# SYZYGY_BOARD_CONN.net
KiCad netlist of a schematic drawn in Altium Designer
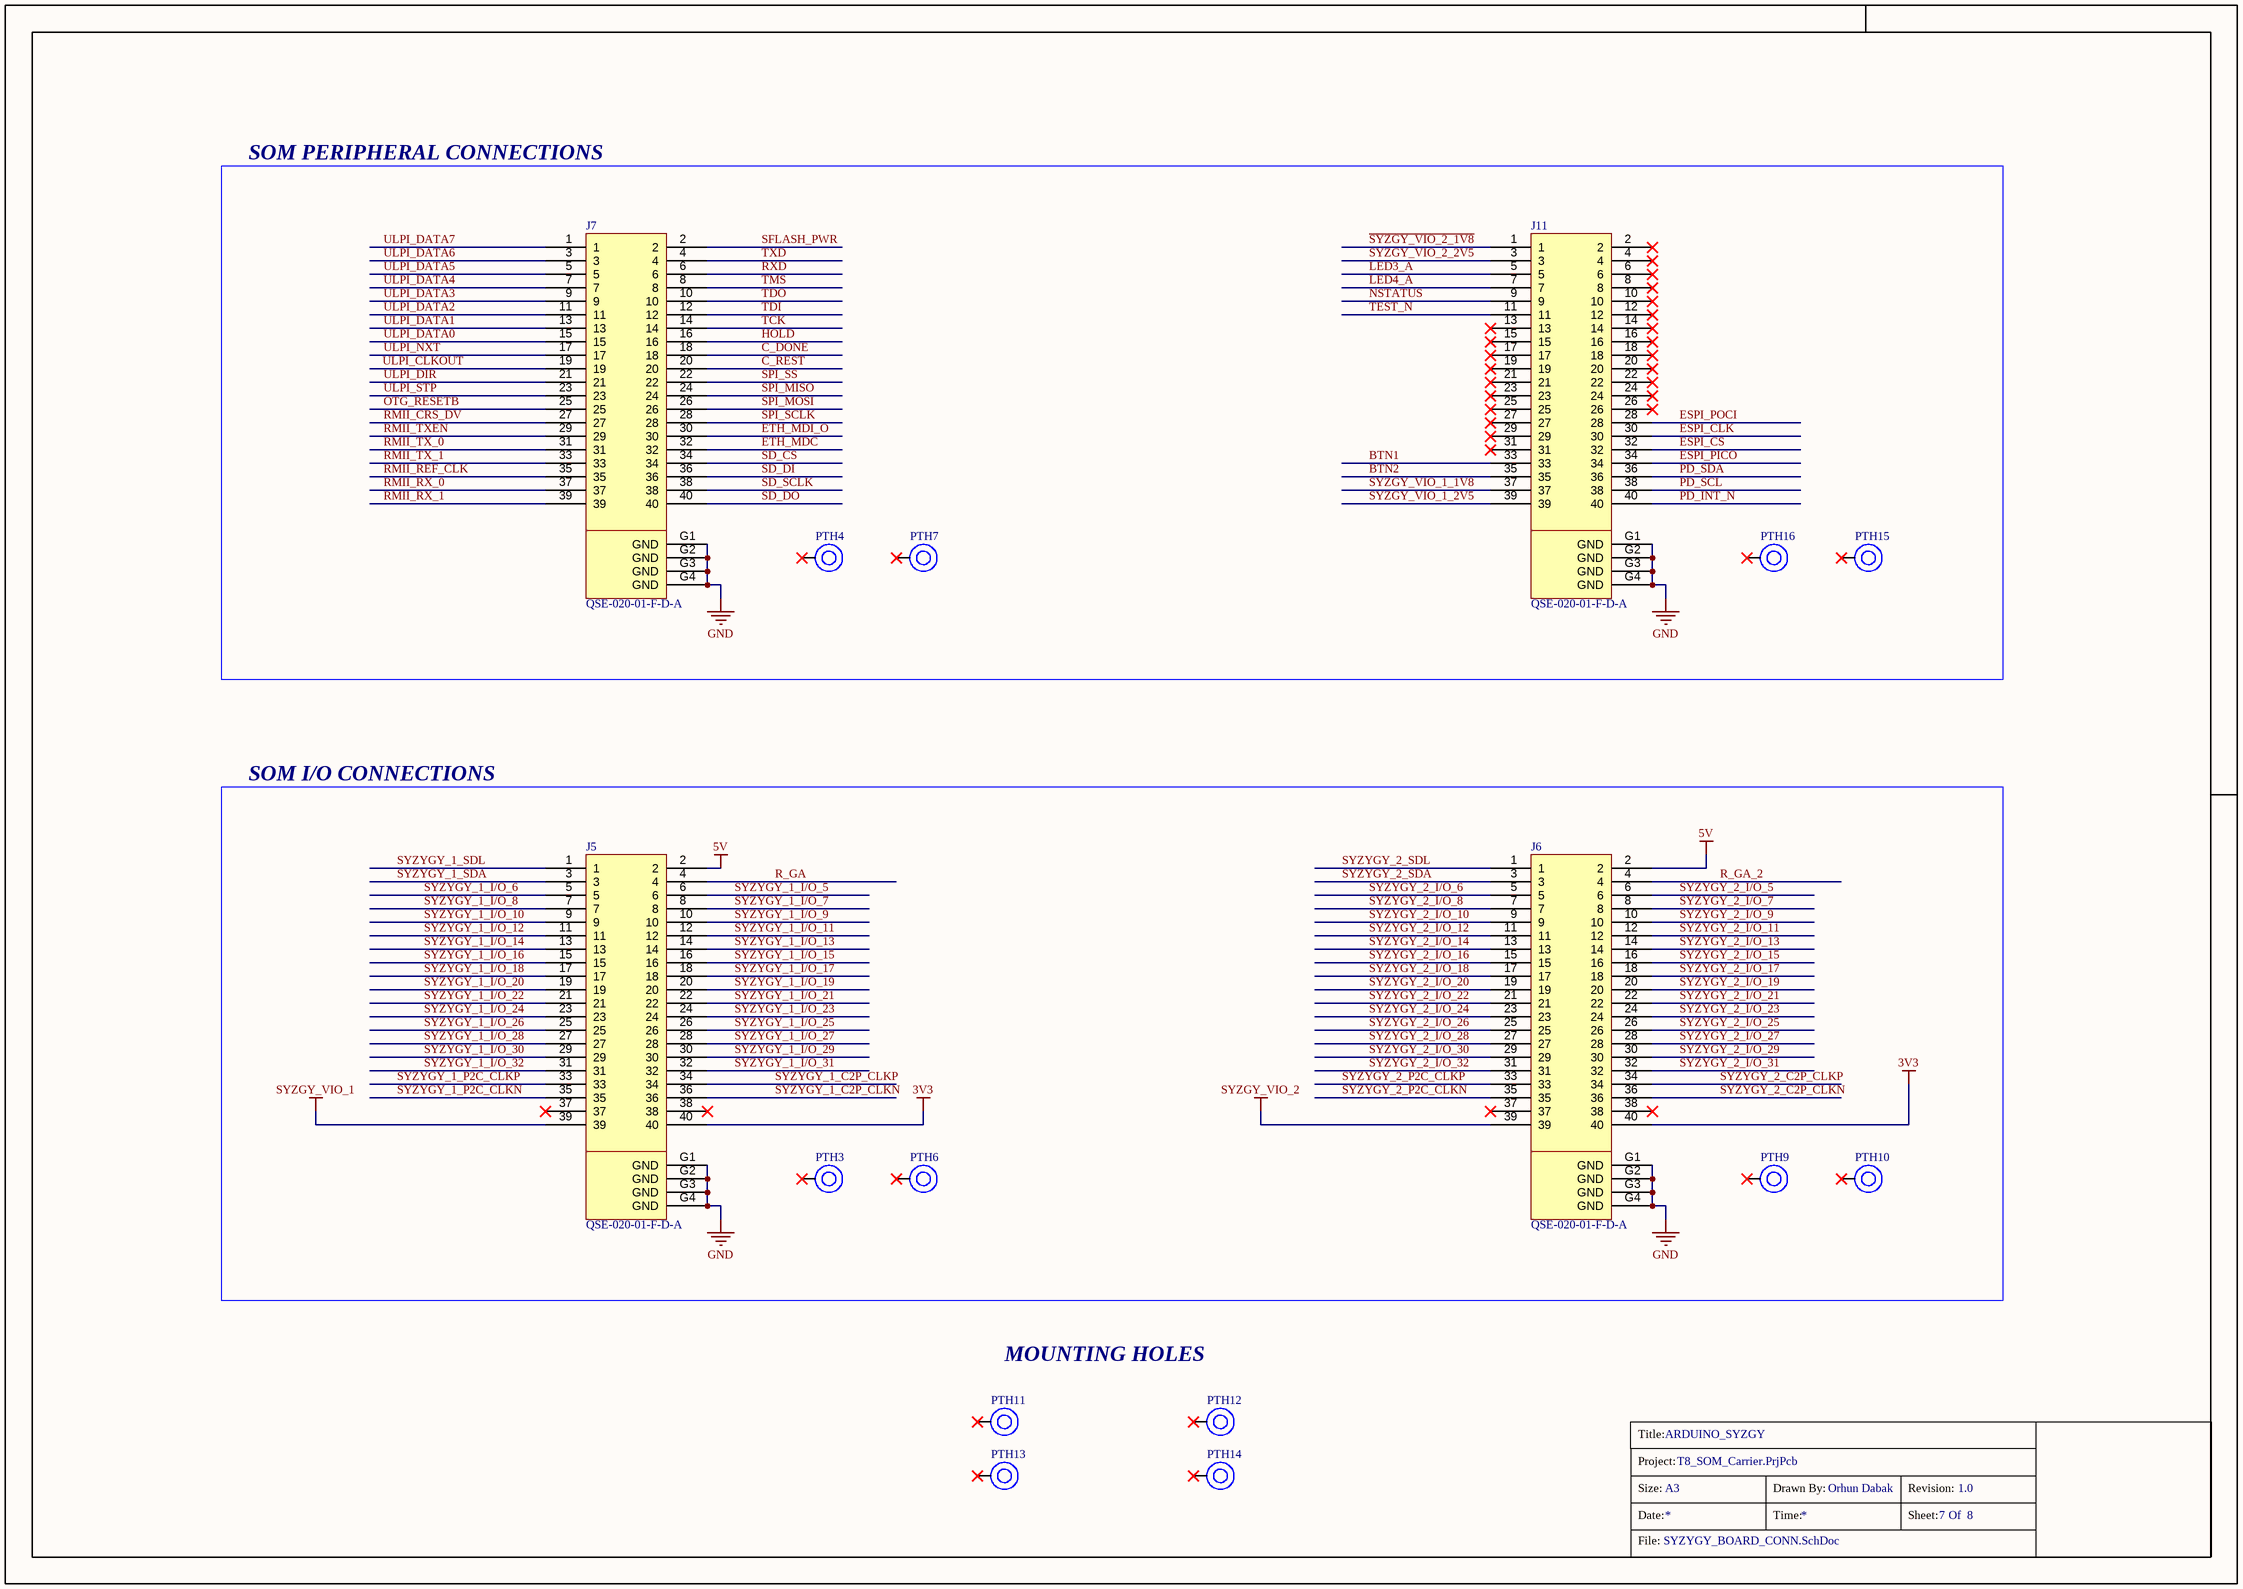
[diagram p0: SYZYGY_BOARD_CONN.SchDoc]

(export (version "E")
  (design (tool "Eeschema 10.0.6"))
  (components
    (comp (ref "J5")
      (value "QSE-020-01-F-D-A")
      (footprint "Components - 26.11.22 - 19.48:QSE-020-01-F-D-A-Footprint-2")
      (description "Conn High Speed Socket Strip SKT 40 POS 0.8mm Solder ST SMD Tray")
      (libsource (lib "Components - 26.11.22 - 19.48") (part "CMP-002-00073-2_2"))
    )
    (comp (ref "J6")
      (value "QSE-020-01-F-D-A")
      (footprint "Components - 26.11.22 - 19.48:QSE-020-01-F-D-A-Footprint-2")
      (description "Conn High Speed Socket Strip SKT 40 POS 0.8mm Solder ST SMD Tray")
      (libsource (lib "Components - 26.11.22 - 19.48") (part "CMP-002-00073-2_2"))
    )
    (comp (ref "J7")
      (value "QSE-020-01-F-D-A")
      (footprint "Components - 26.11.22 - 19.48:QSE-020-01-F-D-A-Footprint-2")
      (description "Conn High Speed Socket Strip SKT 40 POS 0.8mm Solder ST SMD Tray")
      (libsource (lib "Components - 26.11.22 - 19.48") (part "CMP-002-00073-2_2"))
    )
    (comp (ref "J11")
      (value "QSE-020-01-F-D-A")
      (footprint "Components - 26.11.22 - 19.48:QSE-020-01-F-D-A-Footprint-2")
      (description "Conn High Speed Socket Strip SKT 40 POS 0.8mm Solder ST SMD Tray")
      (libsource (lib "Components - 26.11.22 - 19.48") (part "CMP-002-00073-2_2"))
    )
    (comp (ref "PTH3")
      (value "SYZYGY_PCB_Mounting_Hole")
      (footprint "SYZYGY_PCB_Mounting_Hole")
      (libsource (lib "T8_devkit_PCB") (part "SYZYGY_PCB_Mounting_Hole"))
    )
    (comp (ref "PTH4")
      (value "SYZYGY_PCB_Mounting_Hole")
      (footprint "SYZYGY_PCB_Mounting_Hole")
      (libsource (lib "T8_devkit_PCB") (part "SYZYGY_PCB_Mounting_Hole"))
    )
    (comp (ref "PTH6")
      (value "SYZYGY_PCB_Mounting_Hole")
      (footprint "SYZYGY_PCB_Mounting_Hole")
      (libsource (lib "T8_devkit_PCB") (part "SYZYGY_PCB_Mounting_Hole"))
    )
    (comp (ref "PTH7")
      (value "SYZYGY_PCB_Mounting_Hole")
      (footprint "SYZYGY_PCB_Mounting_Hole")
      (libsource (lib "T8_devkit_PCB") (part "SYZYGY_PCB_Mounting_Hole"))
    )
    (comp (ref "PTH9")
      (value "SYZYGY_PCB_Mounting_Hole")
      (footprint "SYZYGY_PCB_Mounting_Hole")
      (libsource (lib "T8_devkit_PCB") (part "SYZYGY_PCB_Mounting_Hole"))
    )
    (comp (ref "PTH10")
      (value "SYZYGY_PCB_Mounting_Hole")
      (footprint "SYZYGY_PCB_Mounting_Hole")
      (libsource (lib "T8_devkit_PCB") (part "SYZYGY_PCB_Mounting_Hole"))
    )
    (comp (ref "PTH11")
      (value "SYZYGY_PCB_Mounting_Hole")
      (footprint "SYZYGY_PCB_Mounting_Hole")
      (libsource (lib "T8_devkit_PCB") (part "SYZYGY_PCB_Mounting_Hole"))
    )
    (comp (ref "PTH12")
      (value "SYZYGY_PCB_Mounting_Hole")
      (footprint "SYZYGY_PCB_Mounting_Hole")
      (libsource (lib "T8_devkit_PCB") (part "SYZYGY_PCB_Mounting_Hole"))
    )
    (comp (ref "PTH13")
      (value "SYZYGY_PCB_Mounting_Hole")
      (footprint "SYZYGY_PCB_Mounting_Hole")
      (libsource (lib "T8_devkit_PCB") (part "SYZYGY_PCB_Mounting_Hole"))
    )
    (comp (ref "PTH14")
      (value "SYZYGY_PCB_Mounting_Hole")
      (footprint "SYZYGY_PCB_Mounting_Hole")
      (libsource (lib "T8_devkit_PCB") (part "SYZYGY_PCB_Mounting_Hole"))
    )
    (comp (ref "PTH15")
      (value "SYZYGY_PCB_Mounting_Hole")
      (footprint "SYZYGY_PCB_Mounting_Hole")
      (libsource (lib "T8_devkit_PCB") (part "SYZYGY_PCB_Mounting_Hole"))
    )
    (comp (ref "PTH16")
      (value "SYZYGY_PCB_Mounting_Hole")
      (footprint "SYZYGY_PCB_Mounting_Hole")
      (libsource (lib "T8_devkit_PCB") (part "SYZYGY_PCB_Mounting_Hole"))
    )
  )
  (nets
    (net (code "1") (name "/BTN1") (class "Default")
      (node (ref "J11") (pin "33") (pinfunction "33_33") (pintype "passive"))
    )
    (net (code "2") (name "/BTN2") (class "Default")
      (node (ref "J11") (pin "35") (pinfunction "35_35") (pintype "passive"))
    )
    (net (code "3") (name "/C_DONE") (class "Default")
      (node (ref "J7") (pin "18") (pinfunction "18_18") (pintype "passive"))
    )
    (net (code "4") (name "/C_REST") (class "Default")
      (node (ref "J7") (pin "20") (pinfunction "20_20") (pintype "passive"))
    )
    (net (code "5") (name "/ESPI_CLK") (class "Default")
      (node (ref "J11") (pin "30") (pinfunction "30_30") (pintype "passive"))
    )
    (net (code "6") (name "/ESPI_CS") (class "Default")
      (node (ref "J11") (pin "32") (pinfunction "32_32") (pintype "passive"))
    )
    (net (code "7") (name "/ESPI_PICO") (class "Default")
      (node (ref "J11") (pin "34") (pinfunction "34_34") (pintype "passive"))
    )
    (net (code "8") (name "/ESPI_POCI") (class "Default")
      (node (ref "J11") (pin "28") (pinfunction "28_28") (pintype "passive"))
    )
    (net (code "9") (name "/ETH_MDC") (class "Default")
      (node (ref "J7") (pin "32") (pinfunction "32_32") (pintype "passive"))
    )
    (net (code "10") (name "/ETH_MDI_O") (class "Default")
      (node (ref "J7") (pin "30") (pinfunction "30_30") (pintype "passive"))
    )
    (net (code "11") (name "/HOLD") (class "Default")
      (node (ref "J7") (pin "16") (pinfunction "16_16") (pintype "passive"))
    )
    (net (code "12") (name "/LED3_A") (class "Default")
      (node (ref "J11") (pin "5") (pinfunction "5_5") (pintype "passive"))
    )
    (net (code "13") (name "/LED4_A") (class "Default")
      (node (ref "J11") (pin "7") (pinfunction "7_7") (pintype "passive"))
    )
    (net (code "14") (name "/NSTATUS") (class "Default")
      (node (ref "J11") (pin "9") (pinfunction "9_9") (pintype "passive"))
    )
    (net (code "15") (name "/OTG_RESETB") (class "Default")
      (node (ref "J7") (pin "25") (pinfunction "25_25") (pintype "passive"))
    )
    (net (code "16") (name "/PD_INT_N") (class "Default")
      (node (ref "J11") (pin "40") (pinfunction "40_40") (pintype "passive"))
    )
    (net (code "17") (name "/PD_SCL") (class "Default")
      (node (ref "J11") (pin "38") (pinfunction "38_38") (pintype "passive"))
    )
    (net (code "18") (name "/PD_SDA") (class "Default")
      (node (ref "J11") (pin "36") (pinfunction "36_36") (pintype "passive"))
    )
    (net (code "19") (name "/RMII_CRS_DV") (class "Default")
      (node (ref "J7") (pin "27") (pinfunction "27_27") (pintype "passive"))
    )
    (net (code "20") (name "/RMII_REF_CLK") (class "Default")
      (node (ref "J7") (pin "35") (pinfunction "35_35") (pintype "passive"))
    )
    (net (code "21") (name "/RMII_RX_0") (class "Default")
      (node (ref "J7") (pin "37") (pinfunction "37_37") (pintype "passive"))
    )
    (net (code "22") (name "/RMII_RX_1") (class "Default")
      (node (ref "J7") (pin "39") (pinfunction "39_39") (pintype "passive"))
    )
    (net (code "23") (name "/RMII_TXEN") (class "Default")
      (node (ref "J7") (pin "29") (pinfunction "29_29") (pintype "passive"))
    )
    (net (code "24") (name "/RMII_TX_0") (class "Default")
      (node (ref "J7") (pin "31") (pinfunction "31_31") (pintype "passive"))
    )
    (net (code "25") (name "/RMII_TX_1") (class "Default")
      (node (ref "J7") (pin "33") (pinfunction "33_33") (pintype "passive"))
    )
    (net (code "26") (name "/RXD") (class "Default")
      (node (ref "J7") (pin "6") (pinfunction "6_6") (pintype "passive"))
    )
    (net (code "27") (name "/R_GA") (class "Default")
      (node (ref "J5") (pin "4") (pinfunction "4_4") (pintype "passive"))
    )
    (net (code "28") (name "/R_GA_2") (class "Default")
      (node (ref "J6") (pin "4") (pinfunction "4_4") (pintype "passive"))
    )
    (net (code "29") (name "/SD_DI") (class "Default")
      (node (ref "J7") (pin "36") (pinfunction "36_36") (pintype "passive"))
    )
    (net (code "30") (name "/SD_DO") (class "Default")
      (node (ref "J7") (pin "40") (pinfunction "40_40") (pintype "passive"))
    )
    (net (code "31") (name "/SD_SCLK") (class "Default")
      (node (ref "J7") (pin "38") (pinfunction "38_38") (pintype "passive"))
    )
    (net (code "32") (name "/SFLASH_PWR") (class "Default")
      (node (ref "J7") (pin "2") (pinfunction "2_2") (pintype "passive"))
    )
    (net (code "33") (name "/SPI_MISO") (class "Default")
      (node (ref "J7") (pin "24") (pinfunction "24_24") (pintype "passive"))
    )
    (net (code "34") (name "/SPI_MOSI") (class "Default")
      (node (ref "J7") (pin "26") (pinfunction "26_26") (pintype "passive"))
    )
    (net (code "35") (name "/SPI_SCLK") (class "Default")
      (node (ref "J7") (pin "28") (pinfunction "28_28") (pintype "passive"))
    )
    (net (code "36") (name "/SPI_SS") (class "Default")
      (node (ref "J7") (pin "22") (pinfunction "22_22") (pintype "passive"))
    )
    (net (code "37") (name "/SYZYGY_1_C2P_CLKN") (class "Default")
      (node (ref "J5") (pin "36") (pinfunction "36_36") (pintype "passive"))
    )
    (net (code "38") (name "/SYZYGY_1_C2P_CLKP") (class "Default")
      (node (ref "J5") (pin "34") (pinfunction "34_34") (pintype "passive"))
    )
    (net (code "39") (name "/SYZYGY_1_I{slash}O_5") (class "Default")
      (node (ref "J5") (pin "6") (pinfunction "6_6") (pintype "passive"))
    )
    (net (code "40") (name "/SYZYGY_1_I{slash}O_6") (class "Default")
      (node (ref "J5") (pin "5") (pinfunction "5_5") (pintype "passive"))
    )
    (net (code "41") (name "/SYZYGY_1_I{slash}O_7") (class "Default")
      (node (ref "J5") (pin "8") (pinfunction "8_8") (pintype "passive"))
    )
    (net (code "42") (name "/SYZYGY_1_I{slash}O_8") (class "Default")
      (node (ref "J5") (pin "7") (pinfunction "7_7") (pintype "passive"))
    )
    (net (code "43") (name "/SYZYGY_1_I{slash}O_9") (class "Default")
      (node (ref "J5") (pin "10") (pinfunction "10_10") (pintype "passive"))
    )
    (net (code "44") (name "/SYZYGY_1_I{slash}O_10") (class "Default")
      (node (ref "J5") (pin "9") (pinfunction "9_9") (pintype "passive"))
    )
    (net (code "45") (name "/SYZYGY_1_I{slash}O_11") (class "Default")
      (node (ref "J5") (pin "12") (pinfunction "12_12") (pintype "passive"))
    )
    (net (code "46") (name "/SYZYGY_1_I{slash}O_12") (class "Default")
      (node (ref "J5") (pin "11") (pinfunction "11_11") (pintype "passive"))
    )
    (net (code "47") (name "/SYZYGY_1_I{slash}O_13") (class "Default")
      (node (ref "J5") (pin "14") (pinfunction "14_14") (pintype "passive"))
    )
    (net (code "48") (name "/SYZYGY_1_I{slash}O_14") (class "Default")
      (node (ref "J5") (pin "13") (pinfunction "13_13") (pintype "passive"))
    )
    (net (code "49") (name "/SYZYGY_1_I{slash}O_15") (class "Default")
      (node (ref "J5") (pin "16") (pinfunction "16_16") (pintype "passive"))
    )
    (net (code "50") (name "/SYZYGY_1_I{slash}O_16") (class "Default")
      (node (ref "J5") (pin "15") (pinfunction "15_15") (pintype "passive"))
    )
    (net (code "51") (name "/SYZYGY_1_I{slash}O_17") (class "Default")
      (node (ref "J5") (pin "18") (pinfunction "18_18") (pintype "passive"))
    )
    (net (code "52") (name "/SYZYGY_1_I{slash}O_18") (class "Default")
      (node (ref "J5") (pin "17") (pinfunction "17_17") (pintype "passive"))
    )
    (net (code "53") (name "/SYZYGY_1_I{slash}O_19") (class "Default")
      (node (ref "J5") (pin "20") (pinfunction "20_20") (pintype "passive"))
    )
    (net (code "54") (name "/SYZYGY_1_I{slash}O_20") (class "Default")
      (node (ref "J5") (pin "19") (pinfunction "19_19") (pintype "passive"))
    )
    (net (code "55") (name "/SYZYGY_1_I{slash}O_21") (class "Default")
      (node (ref "J5") (pin "22") (pinfunction "22_22") (pintype "passive"))
    )
    (net (code "56") (name "/SYZYGY_1_I{slash}O_22") (class "Default")
      (node (ref "J5") (pin "21") (pinfunction "21_21") (pintype "passive"))
    )
    (net (code "57") (name "/SYZYGY_1_I{slash}O_23") (class "Default")
      (node (ref "J5") (pin "24") (pinfunction "24_24") (pintype "passive"))
    )
    (net (code "58") (name "/SYZYGY_1_I{slash}O_24") (class "Default")
      (node (ref "J5") (pin "23") (pinfunction "23_23") (pintype "passive"))
    )
    (net (code "59") (name "/SYZYGY_1_I{slash}O_25") (class "Default")
      (node (ref "J5") (pin "26") (pinfunction "26_26") (pintype "passive"))
    )
    (net (code "60") (name "/SYZYGY_1_I{slash}O_26") (class "Default")
      (node (ref "J5") (pin "25") (pinfunction "25_25") (pintype "passive"))
    )
    (net (code "61") (name "/SYZYGY_1_I{slash}O_27") (class "Default")
      (node (ref "J5") (pin "28") (pinfunction "28_28") (pintype "passive"))
    )
    (net (code "62") (name "/SYZYGY_1_I{slash}O_28") (class "Default")
      (node (ref "J5") (pin "27") (pinfunction "27_27") (pintype "passive"))
    )
    (net (code "63") (name "/SYZYGY_1_I{slash}O_29") (class "Default")
      (node (ref "J5") (pin "30") (pinfunction "30_30") (pintype "passive"))
    )
    (net (code "64") (name "/SYZYGY_1_I{slash}O_30") (class "Default")
      (node (ref "J5") (pin "29") (pinfunction "29_29") (pintype "passive"))
    )
    (net (code "65") (name "/SYZYGY_1_I{slash}O_31") (class "Default")
      (node (ref "J5") (pin "32") (pinfunction "32_32") (pintype "passive"))
    )
    (net (code "66") (name "/SYZYGY_1_I{slash}O_32") (class "Default")
      (node (ref "J5") (pin "31") (pinfunction "31_31") (pintype "passive"))
    )
    (net (code "67") (name "/SYZYGY_1_P2C_CLKN") (class "Default")
      (node (ref "J5") (pin "35") (pinfunction "35_35") (pintype "passive"))
    )
    (net (code "68") (name "/SYZYGY_1_P2C_CLKP") (class "Default")
      (node (ref "J5") (pin "33") (pinfunction "33_33") (pintype "passive"))
    )
    (net (code "69") (name "/SYZYGY_1_SDA") (class "Default")
      (node (ref "J5") (pin "3") (pinfunction "3_3") (pintype "passive"))
    )
    (net (code "70") (name "/SYZYGY_1_SDL") (class "Default")
      (node (ref "J5") (pin "1") (pinfunction "1_1") (pintype "passive"))
    )
    (net (code "71") (name "/SYZYGY_2_C2P_CLKN") (class "Default")
      (node (ref "J6") (pin "36") (pinfunction "36_36") (pintype "passive"))
    )
    (net (code "72") (name "/SYZYGY_2_C2P_CLKP") (class "Default")
      (node (ref "J6") (pin "34") (pinfunction "34_34") (pintype "passive"))
    )
    (net (code "73") (name "/SYZYGY_2_I{slash}O_5") (class "Default")
      (node (ref "J6") (pin "6") (pinfunction "6_6") (pintype "passive"))
    )
    (net (code "74") (name "/SYZYGY_2_I{slash}O_6") (class "Default")
      (node (ref "J6") (pin "5") (pinfunction "5_5") (pintype "passive"))
    )
    (net (code "75") (name "/SYZYGY_2_I{slash}O_7") (class "Default")
      (node (ref "J6") (pin "8") (pinfunction "8_8") (pintype "passive"))
    )
    (net (code "76") (name "/SYZYGY_2_I{slash}O_8") (class "Default")
      (node (ref "J6") (pin "7") (pinfunction "7_7") (pintype "passive"))
    )
    (net (code "77") (name "/SYZYGY_2_I{slash}O_9") (class "Default")
      (node (ref "J6") (pin "10") (pinfunction "10_10") (pintype "passive"))
    )
    (net (code "78") (name "/SYZYGY_2_I{slash}O_10") (class "Default")
      (node (ref "J6") (pin "9") (pinfunction "9_9") (pintype "passive"))
    )
    (net (code "79") (name "/SYZYGY_2_I{slash}O_11") (class "Default")
      (node (ref "J6") (pin "12") (pinfunction "12_12") (pintype "passive"))
    )
    (net (code "80") (name "/SYZYGY_2_I{slash}O_12") (class "Default")
      (node (ref "J6") (pin "11") (pinfunction "11_11") (pintype "passive"))
    )
    (net (code "81") (name "/SYZYGY_2_I{slash}O_13") (class "Default")
      (node (ref "J6") (pin "14") (pinfunction "14_14") (pintype "passive"))
    )
    (net (code "82") (name "/SYZYGY_2_I{slash}O_14") (class "Default")
      (node (ref "J6") (pin "13") (pinfunction "13_13") (pintype "passive"))
    )
    (net (code "83") (name "/SYZYGY_2_I{slash}O_15") (class "Default")
      (node (ref "J6") (pin "16") (pinfunction "16_16") (pintype "passive"))
    )
    (net (code "84") (name "/SYZYGY_2_I{slash}O_16") (class "Default")
      (node (ref "J6") (pin "15") (pinfunction "15_15") (pintype "passive"))
    )
    (net (code "85") (name "/SYZYGY_2_I{slash}O_17") (class "Default")
      (node (ref "J6") (pin "18") (pinfunction "18_18") (pintype "passive"))
    )
    (net (code "86") (name "/SYZYGY_2_I{slash}O_18") (class "Default")
      (node (ref "J6") (pin "17") (pinfunction "17_17") (pintype "passive"))
    )
    (net (code "87") (name "/SYZYGY_2_I{slash}O_19") (class "Default")
      (node (ref "J6") (pin "20") (pinfunction "20_20") (pintype "passive"))
    )
    (net (code "88") (name "/SYZYGY_2_I{slash}O_20") (class "Default")
      (node (ref "J6") (pin "19") (pinfunction "19_19") (pintype "passive"))
    )
    (net (code "89") (name "/SYZYGY_2_I{slash}O_21") (class "Default")
      (node (ref "J6") (pin "22") (pinfunction "22_22") (pintype "passive"))
    )
    (net (code "90") (name "/SYZYGY_2_I{slash}O_22") (class "Default")
      (node (ref "J6") (pin "21") (pinfunction "21_21") (pintype "passive"))
    )
    (net (code "91") (name "/SYZYGY_2_I{slash}O_23") (class "Default")
      (node (ref "J6") (pin "24") (pinfunction "24_24") (pintype "passive"))
    )
    (net (code "92") (name "/SYZYGY_2_I{slash}O_24") (class "Default")
      (node (ref "J6") (pin "23") (pinfunction "23_23") (pintype "passive"))
    )
    (net (code "93") (name "/SYZYGY_2_I{slash}O_25") (class "Default")
      (node (ref "J6") (pin "26") (pinfunction "26_26") (pintype "passive"))
    )
    (net (code "94") (name "/SYZYGY_2_I{slash}O_26") (class "Default")
      (node (ref "J6") (pin "25") (pinfunction "25_25") (pintype "passive"))
    )
    (net (code "95") (name "/SYZYGY_2_I{slash}O_27") (class "Default")
      (node (ref "J6") (pin "28") (pinfunction "28_28") (pintype "passive"))
    )
    (net (code "96") (name "/SYZYGY_2_I{slash}O_28") (class "Default")
      (node (ref "J6") (pin "27") (pinfunction "27_27") (pintype "passive"))
    )
    (net (code "97") (name "/SYZYGY_2_I{slash}O_29") (class "Default")
      (node (ref "J6") (pin "30") (pinfunction "30_30") (pintype "passive"))
    )
    (net (code "98") (name "/SYZYGY_2_I{slash}O_30") (class "Default")
      (node (ref "J6") (pin "29") (pinfunction "29_29") (pintype "passive"))
    )
    (net (code "99") (name "/SYZYGY_2_I{slash}O_31") (class "Default")
      (node (ref "J6") (pin "32") (pinfunction "32_32") (pintype "passive"))
    )
    (net (code "100") (name "/SYZYGY_2_I{slash}O_32") (class "Default")
      (node (ref "J6") (pin "31") (pinfunction "31_31") (pintype "passive"))
    )
    (net (code "101") (name "/SYZYGY_2_P2C_CLKN") (class "Default")
      (node (ref "J6") (pin "35") (pinfunction "35_35") (pintype "passive"))
    )
    (net (code "102") (name "/SYZYGY_2_P2C_CLKP") (class "Default")
      (node (ref "J6") (pin "33") (pinfunction "33_33") (pintype "passive"))
    )
    (net (code "103") (name "/SYZYGY_2_SDA") (class "Default")
      (node (ref "J6") (pin "3") (pinfunction "3_3") (pintype "passive"))
    )
    (net (code "104") (name "/SYZYGY_2_SDL") (class "Default")
      (node (ref "J6") (pin "1") (pinfunction "1_1") (pintype "passive"))
    )
    (net (code "105") (name "/TCK") (class "Default")
      (node (ref "J7") (pin "14") (pinfunction "14_14") (pintype "passive"))
    )
    (net (code "106") (name "/TDI") (class "Default")
      (node (ref "J7") (pin "12") (pinfunction "12_12") (pintype "passive"))
    )
    (net (code "107") (name "/TDO") (class "Default")
      (node (ref "J7") (pin "10") (pinfunction "10_10") (pintype "passive"))
    )
    (net (code "108") (name "/TEST_N") (class "Default")
      (node (ref "J11") (pin "11") (pinfunction "11_11") (pintype "passive"))
    )
    (net (code "109") (name "/TMS") (class "Default")
      (node (ref "J7") (pin "8") (pinfunction "8_8") (pintype "passive"))
    )
    (net (code "110") (name "/TXD") (class "Default")
      (node (ref "J7") (pin "4") (pinfunction "4_4") (pintype "passive"))
    )
    (net (code "111") (name "/ULPI_CLKOUT") (class "Default")
      (node (ref "J7") (pin "19") (pinfunction "19_19") (pintype "passive"))
    )
    (net (code "112") (name "/ULPI_DATA0") (class "Default")
      (node (ref "J7") (pin "15") (pinfunction "15_15") (pintype "passive"))
    )
    (net (code "113") (name "/ULPI_DATA1") (class "Default")
      (node (ref "J7") (pin "13") (pinfunction "13_13") (pintype "passive"))
    )
    (net (code "114") (name "/ULPI_DATA2") (class "Default")
      (node (ref "J7") (pin "11") (pinfunction "11_11") (pintype "passive"))
    )
    (net (code "115") (name "/ULPI_DATA3") (class "Default")
      (node (ref "J7") (pin "9") (pinfunction "9_9") (pintype "passive"))
    )
    (net (code "116") (name "/ULPI_DATA4") (class "Default")
      (node (ref "J7") (pin "7") (pinfunction "7_7") (pintype "passive"))
    )
    (net (code "117") (name "/ULPI_DATA5") (class "Default")
      (node (ref "J7") (pin "5") (pinfunction "5_5") (pintype "passive"))
    )
    (net (code "118") (name "/ULPI_DATA6") (class "Default")
      (node (ref "J7") (pin "3") (pinfunction "3_3") (pintype "passive"))
    )
    (net (code "119") (name "/ULPI_DATA7") (class "Default")
      (node (ref "J7") (pin "1") (pinfunction "1_1") (pintype "passive"))
    )
    (net (code "120") (name "/ULPI_DIR") (class "Default")
      (node (ref "J7") (pin "21") (pinfunction "21_21") (pintype "passive"))
    )
    (net (code "121") (name "/ULPI_NXT") (class "Default")
      (node (ref "J7") (pin "17") (pinfunction "17_17") (pintype "passive"))
    )
    (net (code "122") (name "/ULPI_STP") (class "Default")
      (node (ref "J7") (pin "23") (pinfunction "23_23") (pintype "passive"))
    )
    (net (code "123") (name "/~{SD_CS}") (class "Default")
      (node (ref "J7") (pin "34") (pinfunction "34_34") (pintype "passive"))
    )
    (net (code "124") (name "/~{SYZGY_VIO_1_1V8}") (class "Default")
      (node (ref "J11") (pin "37") (pinfunction "37_37") (pintype "passive"))
    )
    (net (code "125") (name "/~{SYZGY_VIO_1_2V5}") (class "Default")
      (node (ref "J11") (pin "39") (pinfunction "39_39") (pintype "passive"))
    )
    (net (code "126") (name "/~{SYZGY_VIO_2_1V8}") (class "Default")
      (node (ref "J11") (pin "1") (pinfunction "1_1") (pintype "passive"))
    )
    (net (code "127") (name "/~{SYZGY_VIO_2_2V5}") (class "Default")
      (node (ref "J11") (pin "3") (pinfunction "3_3") (pintype "passive"))
    )
    (net (code "128") (name "3V3") (class "Default")
      (node (ref "J5") (pin "40") (pinfunction "40_40") (pintype "passive"))
      (node (ref "J6") (pin "40") (pinfunction "40_40") (pintype "passive"))
    )
    (net (code "129") (name "5V") (class "Default")
      (node (ref "J5") (pin "2") (pinfunction "2_2") (pintype "passive"))
      (node (ref "J6") (pin "2") (pinfunction "2_2") (pintype "passive"))
    )
    (net (code "130") (name "GND") (class "Default")
      (node (ref "J11") (pin "G1") (pinfunction "GND_G1") (pintype "power_in"))
      (node (ref "J11") (pin "G2") (pinfunction "GND_G2") (pintype "power_in"))
      (node (ref "J11") (pin "G3") (pinfunction "GND_G3") (pintype "power_in"))
      (node (ref "J11") (pin "G4") (pinfunction "GND_G4") (pintype "power_in"))
      (node (ref "J5") (pin "G1") (pinfunction "GND_G1") (pintype "power_in"))
      (node (ref "J5") (pin "G2") (pinfunction "GND_G2") (pintype "power_in"))
      (node (ref "J5") (pin "G3") (pinfunction "GND_G3") (pintype "power_in"))
      (node (ref "J5") (pin "G4") (pinfunction "GND_G4") (pintype "power_in"))
      (node (ref "J6") (pin "G1") (pinfunction "GND_G1") (pintype "power_in"))
      (node (ref "J6") (pin "G2") (pinfunction "GND_G2") (pintype "power_in"))
      (node (ref "J6") (pin "G3") (pinfunction "GND_G3") (pintype "power_in"))
      (node (ref "J6") (pin "G4") (pinfunction "GND_G4") (pintype "power_in"))
      (node (ref "J7") (pin "G1") (pinfunction "GND_G1") (pintype "power_in"))
      (node (ref "J7") (pin "G2") (pinfunction "GND_G2") (pintype "power_in"))
      (node (ref "J7") (pin "G3") (pinfunction "GND_G3") (pintype "power_in"))
      (node (ref "J7") (pin "G4") (pinfunction "GND_G4") (pintype "power_in"))
    )
    (net (code "131") (name "SYZGY_VIO_1") (class "Default")
      (node (ref "J5") (pin "39") (pinfunction "39_39") (pintype "passive"))
    )
    (net (code "132") (name "SYZGY_VIO_2") (class "Default")
      (node (ref "J6") (pin "39") (pinfunction "39_39") (pintype "passive"))
    )
    (net (code "133") (name "unconnected-(J5-Pad37)") (class "Default")
      (node (ref "J5") (pin "37") (pinfunction "37_37") (pintype "passive+no_connect"))
    )
    (net (code "134") (name "unconnected-(J5-Pad38)") (class "Default")
      (node (ref "J5") (pin "38") (pinfunction "38_38") (pintype "passive+no_connect"))
    )
    (net (code "135") (name "unconnected-(J6-Pad37)") (class "Default")
      (node (ref "J6") (pin "37") (pinfunction "37_37") (pintype "passive+no_connect"))
    )
    (net (code "136") (name "unconnected-(J6-Pad38)") (class "Default")
      (node (ref "J6") (pin "38") (pinfunction "38_38") (pintype "passive+no_connect"))
    )
    (net (code "137") (name "unconnected-(J11-Pad2)") (class "Default")
      (node (ref "J11") (pin "2") (pinfunction "2_2") (pintype "passive+no_connect"))
    )
    (net (code "138") (name "unconnected-(J11-Pad4)") (class "Default")
      (node (ref "J11") (pin "4") (pinfunction "4_4") (pintype "passive+no_connect"))
    )
    (net (code "139") (name "unconnected-(J11-Pad6)") (class "Default")
      (node (ref "J11") (pin "6") (pinfunction "6_6") (pintype "passive+no_connect"))
    )
    (net (code "140") (name "unconnected-(J11-Pad8)") (class "Default")
      (node (ref "J11") (pin "8") (pinfunction "8_8") (pintype "passive+no_connect"))
    )
    (net (code "141") (name "unconnected-(J11-Pad10)") (class "Default")
      (node (ref "J11") (pin "10") (pinfunction "10_10") (pintype "passive+no_connect"))
    )
    (net (code "142") (name "unconnected-(J11-Pad12)") (class "Default")
      (node (ref "J11") (pin "12") (pinfunction "12_12") (pintype "passive+no_connect"))
    )
    (net (code "143") (name "unconnected-(J11-Pad13)") (class "Default")
      (node (ref "J11") (pin "13") (pinfunction "13_13") (pintype "passive+no_connect"))
    )
    (net (code "144") (name "unconnected-(J11-Pad14)") (class "Default")
      (node (ref "J11") (pin "14") (pinfunction "14_14") (pintype "passive+no_connect"))
    )
    (net (code "145") (name "unconnected-(J11-Pad15)") (class "Default")
      (node (ref "J11") (pin "15") (pinfunction "15_15") (pintype "passive+no_connect"))
    )
    (net (code "146") (name "unconnected-(J11-Pad16)") (class "Default")
      (node (ref "J11") (pin "16") (pinfunction "16_16") (pintype "passive+no_connect"))
    )
    (net (code "147") (name "unconnected-(J11-Pad17)") (class "Default")
      (node (ref "J11") (pin "17") (pinfunction "17_17") (pintype "passive+no_connect"))
    )
    (net (code "148") (name "unconnected-(J11-Pad18)") (class "Default")
      (node (ref "J11") (pin "18") (pinfunction "18_18") (pintype "passive+no_connect"))
    )
    (net (code "149") (name "unconnected-(J11-Pad19)") (class "Default")
      (node (ref "J11") (pin "19") (pinfunction "19_19") (pintype "passive+no_connect"))
    )
    (net (code "150") (name "unconnected-(J11-Pad20)") (class "Default")
      (node (ref "J11") (pin "20") (pinfunction "20_20") (pintype "passive+no_connect"))
    )
    (net (code "151") (name "unconnected-(J11-Pad21)") (class "Default")
      (node (ref "J11") (pin "21") (pinfunction "21_21") (pintype "passive+no_connect"))
    )
    (net (code "152") (name "unconnected-(J11-Pad22)") (class "Default")
      (node (ref "J11") (pin "22") (pinfunction "22_22") (pintype "passive+no_connect"))
    )
    (net (code "153") (name "unconnected-(J11-Pad23)") (class "Default")
      (node (ref "J11") (pin "23") (pinfunction "23_23") (pintype "passive+no_connect"))
    )
    (net (code "154") (name "unconnected-(J11-Pad24)") (class "Default")
      (node (ref "J11") (pin "24") (pinfunction "24_24") (pintype "passive+no_connect"))
    )
    (net (code "155") (name "unconnected-(J11-Pad25)") (class "Default")
      (node (ref "J11") (pin "25") (pinfunction "25_25") (pintype "passive+no_connect"))
    )
    (net (code "156") (name "unconnected-(J11-Pad26)") (class "Default")
      (node (ref "J11") (pin "26") (pinfunction "26_26") (pintype "passive+no_connect"))
    )
    (net (code "157") (name "unconnected-(J11-Pad27)") (class "Default")
      (node (ref "J11") (pin "27") (pinfunction "27_27") (pintype "passive+no_connect"))
    )
    (net (code "158") (name "unconnected-(J11-Pad29)") (class "Default")
      (node (ref "J11") (pin "29") (pinfunction "29_29") (pintype "passive+no_connect"))
    )
    (net (code "159") (name "unconnected-(J11-Pad31)") (class "Default")
      (node (ref "J11") (pin "31") (pinfunction "31_31") (pintype "passive+no_connect"))
    )
    (net (code "160") (name "unconnected-(PTH3-Pad1)") (class "Default")
      (node (ref "PTH3") (pin "1") (pinfunction "1_1") (pintype "passive+no_connect"))
    )
    (net (code "161") (name "unconnected-(PTH4-Pad1)") (class "Default")
      (node (ref "PTH4") (pin "1") (pinfunction "1_1") (pintype "passive+no_connect"))
    )
    (net (code "162") (name "unconnected-(PTH6-Pad1)") (class "Default")
      (node (ref "PTH6") (pin "1") (pinfunction "1_1") (pintype "passive+no_connect"))
    )
    (net (code "163") (name "unconnected-(PTH7-Pad1)") (class "Default")
      (node (ref "PTH7") (pin "1") (pinfunction "1_1") (pintype "passive+no_connect"))
    )
    (net (code "164") (name "unconnected-(PTH9-Pad1)") (class "Default")
      (node (ref "PTH9") (pin "1") (pinfunction "1_1") (pintype "passive+no_connect"))
    )
    (net (code "165") (name "unconnected-(PTH10-Pad1)") (class "Default")
      (node (ref "PTH10") (pin "1") (pinfunction "1_1") (pintype "passive+no_connect"))
    )
    (net (code "166") (name "unconnected-(PTH11-Pad1)") (class "Default")
      (node (ref "PTH11") (pin "1") (pinfunction "1_1") (pintype "passive+no_connect"))
    )
    (net (code "167") (name "unconnected-(PTH12-Pad1)") (class "Default")
      (node (ref "PTH12") (pin "1") (pinfunction "1_1") (pintype "passive+no_connect"))
    )
    (net (code "168") (name "unconnected-(PTH13-Pad1)") (class "Default")
      (node (ref "PTH13") (pin "1") (pinfunction "1_1") (pintype "passive+no_connect"))
    )
    (net (code "169") (name "unconnected-(PTH14-Pad1)") (class "Default")
      (node (ref "PTH14") (pin "1") (pinfunction "1_1") (pintype "passive+no_connect"))
    )
    (net (code "170") (name "unconnected-(PTH15-Pad1)") (class "Default")
      (node (ref "PTH15") (pin "1") (pinfunction "1_1") (pintype "passive+no_connect"))
    )
    (net (code "171") (name "unconnected-(PTH16-Pad1)") (class "Default")
      (node (ref "PTH16") (pin "1") (pinfunction "1_1") (pintype "passive+no_connect"))
    )
  )
)
